# copper.net
KiCad netlist of a schematic drawn in EAGLE
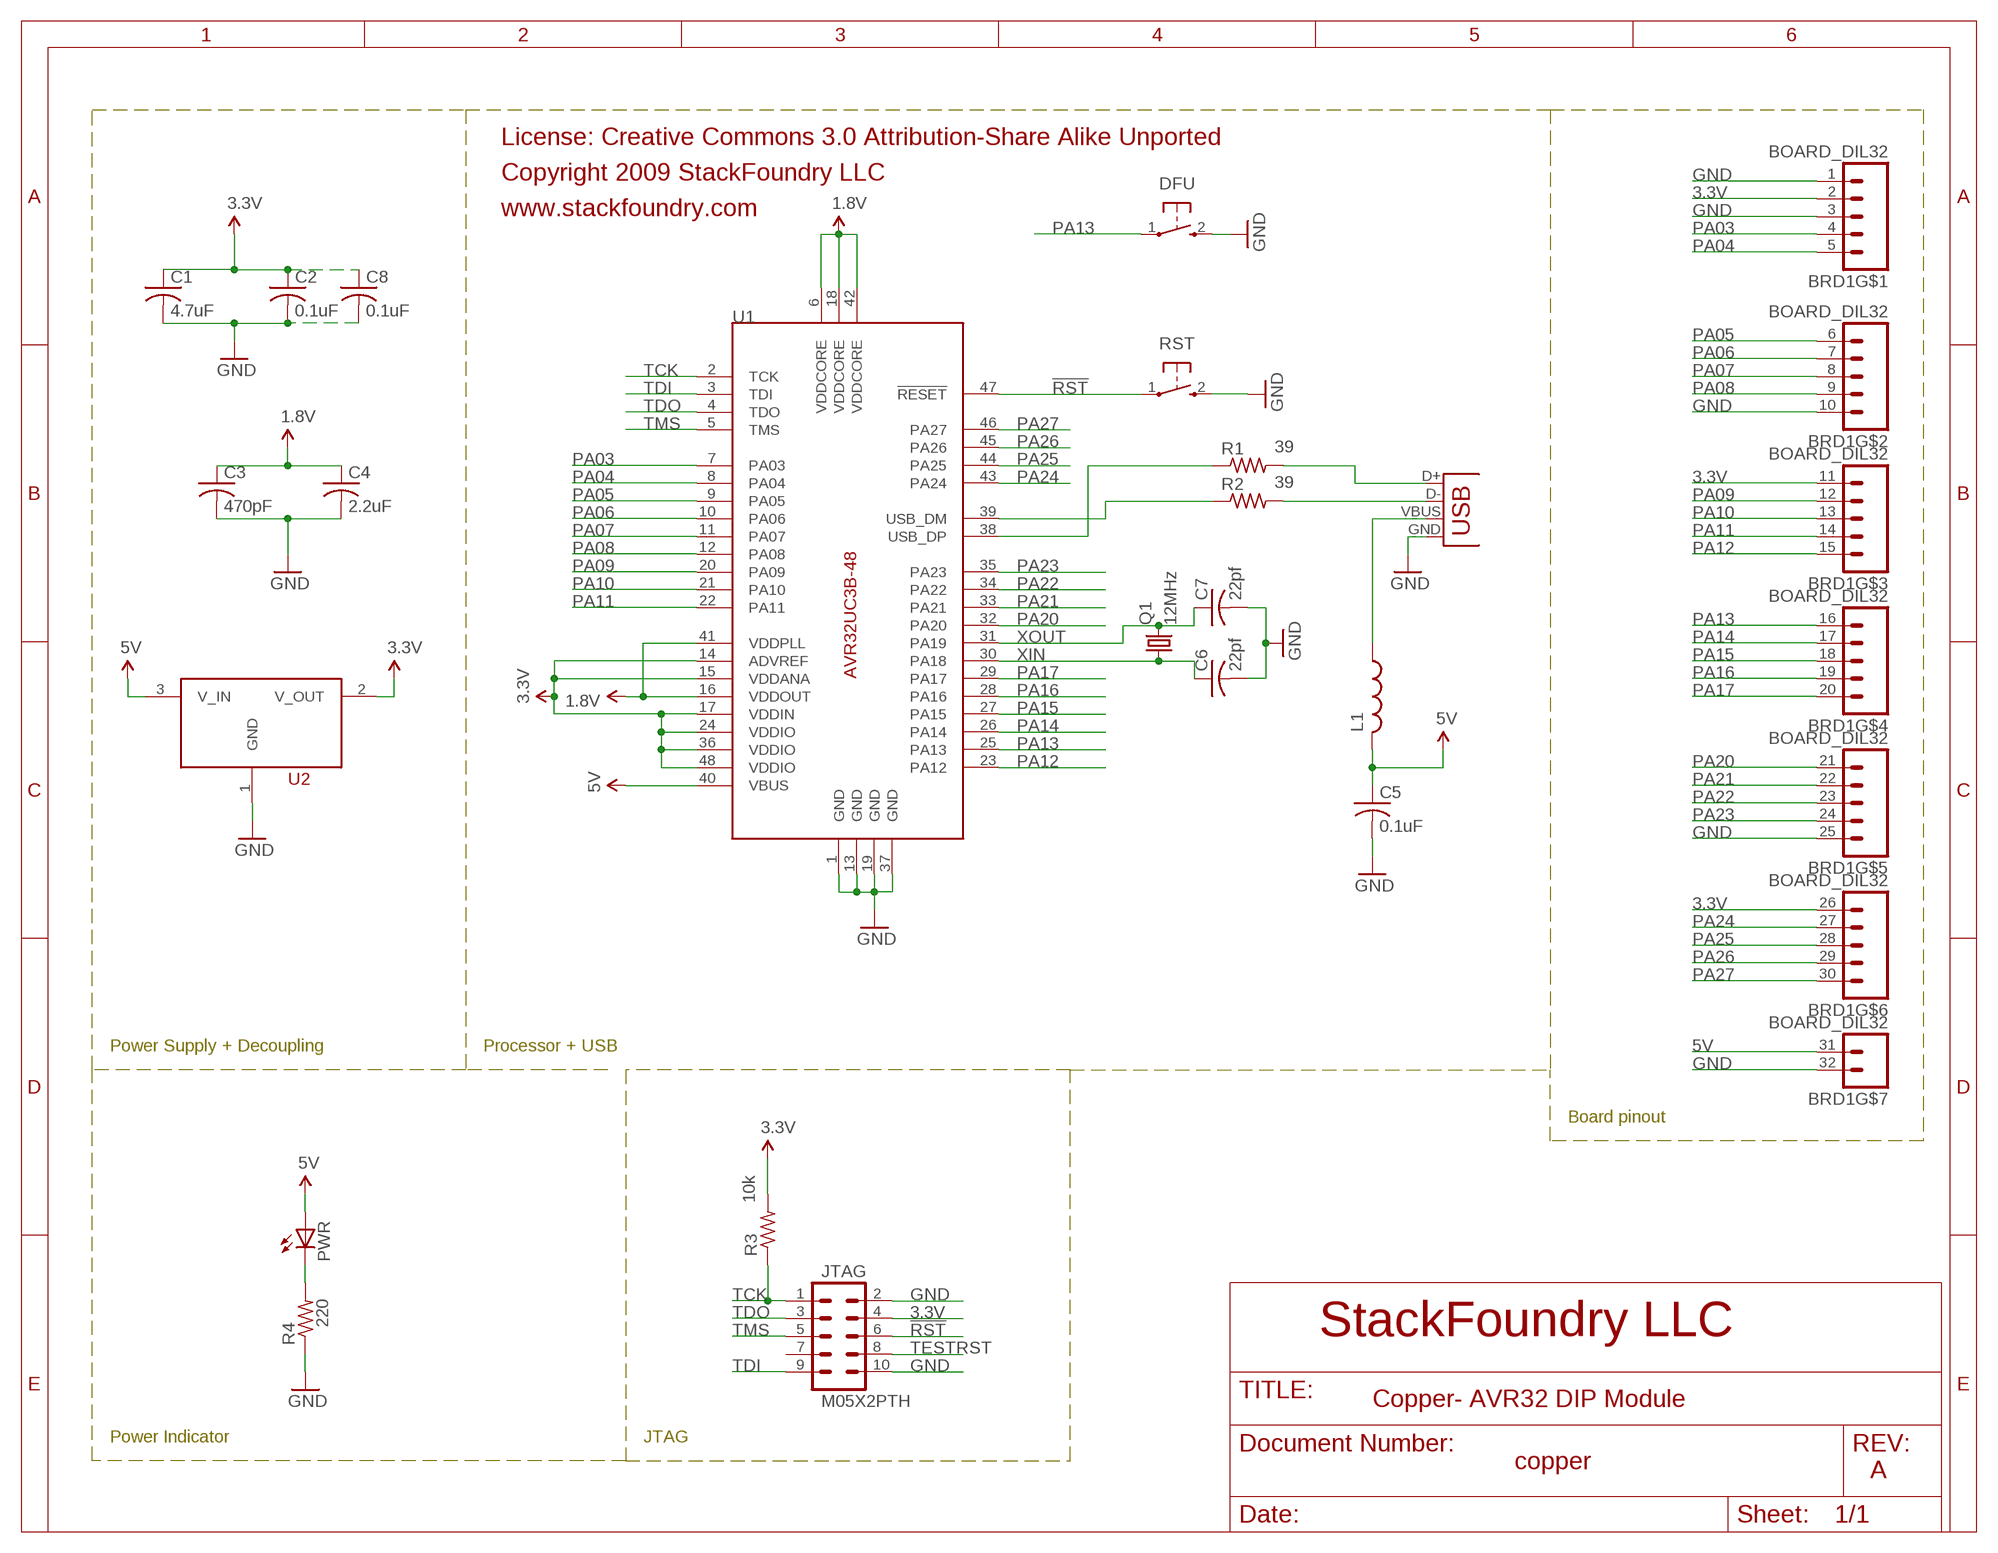
[diagram p0: schematic, sheet 1]

(export (version "E")
  (design (tool "Eeschema 10.0.6"))
  (components
    (comp (ref "BRD1")
      (value "BOARD_DIL32")
      (footprint "eagle-import:DIL32-NOSILK")
      (libsource (lib "eagle-import") (part "BOARD_DIL32"))
    )
    (comp (ref "C1")
      (value "4.7uF")
      (footprint "eagle-import:C0603")
      (libsource (lib "eagle-import") (part "C-USC0603"))
    )
    (comp (ref "C2")
      (value "0.1uF")
      (footprint "eagle-import:C0603")
      (libsource (lib "eagle-import") (part "C-USC0603"))
    )
    (comp (ref "C3")
      (value "470pF")
      (footprint "eagle-import:C0603")
      (libsource (lib "eagle-import") (part "C-USC0603"))
    )
    (comp (ref "C4")
      (value "2.2uF")
      (footprint "eagle-import:C0603")
      (libsource (lib "eagle-import") (part "C-USC0603"))
    )
    (comp (ref "C5")
      (value "0.1uF")
      (footprint "eagle-import:C0603")
      (libsource (lib "eagle-import") (part "C-USC0603"))
    )
    (comp (ref "C6")
      (value "22pf")
      (footprint "eagle-import:C0603")
      (libsource (lib "eagle-import") (part "C-USC0603"))
    )
    (comp (ref "C7")
      (value "22pf")
      (footprint "eagle-import:C0603")
      (libsource (lib "eagle-import") (part "C-USC0603"))
    )
    (comp (ref "C8")
      (value "0.1uF")
      (footprint "eagle-import:C0603")
      (libsource (lib "eagle-import") (part "C-USC0603"))
    )
    (comp (ref "DFU")
      (value "TAC_SWITCH_2PB3U")
      (footprint "eagle-import:OMROM_B3U")
      (libsource (lib "eagle-import") (part "TAC_SWITCH_2PB3U"))
    )
    (comp (ref "JTAG")
      (value "M05X2PTH")
      (footprint "eagle-import:AVR_ICSP")
      (libsource (lib "eagle-import") (part "M05X2PTH"))
    )
    (comp (ref "L1")
      (value "L-USL0805")
      (footprint "eagle-import:L0805")
      (libsource (lib "eagle-import") (part "L-USL0805"))
    )
    (comp (ref "PWR")
      (value "LED1206")
      (footprint "eagle-import:LED-1206")
      (libsource (lib "eagle-import") (part "LED1206"))
    )
    (comp (ref "Q1")
      (value "12MHz")
      (footprint "eagle-import:CRYSTAL-SMD-5X3.2")
      (libsource (lib "eagle-import") (part "CRYSTAL25X3.2"))
    )
    (comp (ref "R1")
      (value "39")
      (footprint "eagle-import:R0603")
      (libsource (lib "eagle-import") (part "R-US_R0603"))
    )
    (comp (ref "R2")
      (value "39")
      (footprint "eagle-import:R0603")
      (libsource (lib "eagle-import") (part "R-US_R0603"))
    )
    (comp (ref "R3")
      (value "10k")
      (footprint "eagle-import:R0603")
      (libsource (lib "eagle-import") (part "R-US_R0603"))
    )
    (comp (ref "R4")
      (value "220")
      (footprint "eagle-import:R0603")
      (libsource (lib "eagle-import") (part "R-US_R0603"))
    )
    (comp (ref "RST")
      (value "TAC_SWITCH_2PB3U")
      (footprint "eagle-import:OMROM_B3U")
      (libsource (lib "eagle-import") (part "TAC_SWITCH_2PB3U"))
    )
    (comp (ref "U1")
      (value "AVR32UC3B-48TQFP")
      (footprint "eagle-import:TQFP48")
      (libsource (lib "eagle-import") (part "AVR32UC3B-48TQFP"))
    )
    (comp (ref "U2")
      (value "MCP1700")
      (footprint "eagle-import:SOT23")
      (libsource (lib "eagle-import") (part "MCP1700"))
    )
    (comp (ref "X2")
      (value "USBSMD")
      (footprint "eagle-import:USB-MINIB")
      (libsource (lib "eagle-import") (part "USBSMD"))
    )
  )
  (nets
    (net (code "1") (name "/PA03") (class "Default")
      (node (ref "BRD1") (pin "4") (pinfunction "4_4") (pintype "passive"))
      (node (ref "U1") (pin "7") (pinfunction "PA03_7") (pintype "bidirectional"))
    )
    (net (code "2") (name "/PA04") (class "Default")
      (node (ref "BRD1") (pin "5") (pinfunction "5_5") (pintype "passive"))
      (node (ref "U1") (pin "8") (pinfunction "PA04_8") (pintype "bidirectional"))
    )
    (net (code "3") (name "/PA05") (class "Default")
      (node (ref "BRD1") (pin "6") (pinfunction "1_6") (pintype "passive"))
      (node (ref "U1") (pin "9") (pinfunction "PA05_9") (pintype "bidirectional"))
    )
    (net (code "4") (name "/PA06") (class "Default")
      (node (ref "BRD1") (pin "7") (pinfunction "2_7") (pintype "passive"))
      (node (ref "U1") (pin "10") (pinfunction "PA06_10") (pintype "bidirectional"))
    )
    (net (code "5") (name "/PA07") (class "Default")
      (node (ref "BRD1") (pin "8") (pinfunction "3_8") (pintype "passive"))
      (node (ref "U1") (pin "11") (pinfunction "PA07_11") (pintype "bidirectional"))
    )
    (net (code "6") (name "/PA08") (class "Default")
      (node (ref "BRD1") (pin "9") (pinfunction "4_9") (pintype "passive"))
      (node (ref "U1") (pin "12") (pinfunction "PA08_12") (pintype "bidirectional"))
    )
    (net (code "7") (name "/PA09") (class "Default")
      (node (ref "BRD1") (pin "12") (pinfunction "2_12") (pintype "passive"))
      (node (ref "U1") (pin "20") (pinfunction "PA09_20") (pintype "bidirectional"))
    )
    (net (code "8") (name "/PA10") (class "Default")
      (node (ref "BRD1") (pin "13") (pinfunction "3_13") (pintype "passive"))
      (node (ref "U1") (pin "21") (pinfunction "PA10_21") (pintype "bidirectional"))
    )
    (net (code "9") (name "/PA11") (class "Default")
      (node (ref "BRD1") (pin "14") (pinfunction "4_14") (pintype "passive"))
      (node (ref "U1") (pin "22") (pinfunction "PA11_22") (pintype "bidirectional"))
    )
    (net (code "10") (name "/PA12") (class "Default")
      (node (ref "BRD1") (pin "15") (pinfunction "5_15") (pintype "passive"))
      (node (ref "U1") (pin "23") (pinfunction "PA12_23") (pintype "bidirectional"))
    )
    (net (code "11") (name "/PA13") (class "Default")
      (node (ref "BRD1") (pin "16") (pinfunction "1_16") (pintype "passive"))
      (node (ref "DFU") (pin "1") (pinfunction "1_1") (pintype "passive"))
      (node (ref "U1") (pin "25") (pinfunction "PA13_25") (pintype "bidirectional"))
    )
    (net (code "12") (name "/PA14") (class "Default")
      (node (ref "BRD1") (pin "17") (pinfunction "2_17") (pintype "passive"))
      (node (ref "U1") (pin "26") (pinfunction "PA14_26") (pintype "bidirectional"))
    )
    (net (code "13") (name "/PA15") (class "Default")
      (node (ref "BRD1") (pin "18") (pinfunction "3_18") (pintype "passive"))
      (node (ref "U1") (pin "27") (pinfunction "PA15_27") (pintype "bidirectional"))
    )
    (net (code "14") (name "/PA16") (class "Default")
      (node (ref "BRD1") (pin "19") (pinfunction "4_19") (pintype "passive"))
      (node (ref "U1") (pin "28") (pinfunction "PA16_28") (pintype "bidirectional"))
    )
    (net (code "15") (name "/PA17") (class "Default")
      (node (ref "BRD1") (pin "20") (pinfunction "5_20") (pintype "passive"))
      (node (ref "U1") (pin "29") (pinfunction "PA17_29") (pintype "bidirectional"))
    )
    (net (code "16") (name "/PA20") (class "Default")
      (node (ref "BRD1") (pin "21") (pinfunction "1_21") (pintype "passive"))
      (node (ref "U1") (pin "32") (pinfunction "PA20_32") (pintype "bidirectional"))
    )
    (net (code "17") (name "/PA21") (class "Default")
      (node (ref "BRD1") (pin "22") (pinfunction "2_22") (pintype "passive"))
      (node (ref "U1") (pin "33") (pinfunction "PA21_33") (pintype "bidirectional"))
    )
    (net (code "18") (name "/PA22") (class "Default")
      (node (ref "BRD1") (pin "23") (pinfunction "3_23") (pintype "passive"))
      (node (ref "U1") (pin "34") (pinfunction "PA22_34") (pintype "bidirectional"))
    )
    (net (code "19") (name "/PA23") (class "Default")
      (node (ref "BRD1") (pin "24") (pinfunction "4_24") (pintype "passive"))
      (node (ref "U1") (pin "35") (pinfunction "PA23_35") (pintype "bidirectional"))
    )
    (net (code "20") (name "/PA24") (class "Default")
      (node (ref "BRD1") (pin "27") (pinfunction "2_27") (pintype "passive"))
      (node (ref "U1") (pin "43") (pinfunction "PA24_43") (pintype "bidirectional"))
    )
    (net (code "21") (name "/PA25") (class "Default")
      (node (ref "BRD1") (pin "28") (pinfunction "3_28") (pintype "passive"))
      (node (ref "U1") (pin "44") (pinfunction "PA25_44") (pintype "bidirectional"))
    )
    (net (code "22") (name "/PA26") (class "Default")
      (node (ref "BRD1") (pin "29") (pinfunction "4_29") (pintype "passive"))
      (node (ref "U1") (pin "45") (pinfunction "PA26_45") (pintype "bidirectional"))
    )
    (net (code "23") (name "/PA27") (class "Default")
      (node (ref "BRD1") (pin "30") (pinfunction "5_30") (pintype "passive"))
      (node (ref "U1") (pin "46") (pinfunction "PA27_46") (pintype "bidirectional"))
    )
    (net (code "24") (name "/TCK") (class "Default")
      (node (ref "JTAG") (pin "1") (pinfunction "1_1") (pintype "passive"))
      (node (ref "R3") (pin "1") (pinfunction "1_1") (pintype "passive"))
      (node (ref "U1") (pin "2") (pinfunction "TCK_2") (pintype "bidirectional"))
    )
    (net (code "25") (name "/TDI") (class "Default")
      (node (ref "JTAG") (pin "9") (pinfunction "9_9") (pintype "passive"))
      (node (ref "U1") (pin "3") (pinfunction "TDI_3") (pintype "bidirectional"))
    )
    (net (code "26") (name "/TDO") (class "Default")
      (node (ref "JTAG") (pin "3") (pinfunction "3_3") (pintype "passive"))
      (node (ref "U1") (pin "4") (pinfunction "TDO_4") (pintype "bidirectional"))
    )
    (net (code "27") (name "/TESTRST") (class "Default")
      (node (ref "JTAG") (pin "8") (pinfunction "8_8") (pintype "passive"))
    )
    (net (code "28") (name "/TMS") (class "Default")
      (node (ref "JTAG") (pin "5") (pinfunction "5_5") (pintype "passive"))
      (node (ref "U1") (pin "5") (pinfunction "TMS_5") (pintype "bidirectional"))
    )
    (net (code "29") (name "/XIN") (class "Default")
      (node (ref "C6") (pin "1") (pinfunction "1_1") (pintype "passive"))
      (node (ref "Q1") (pin "1") (pinfunction "1_1") (pintype "passive"))
      (node (ref "U1") (pin "30") (pinfunction "PA18_30") (pintype "bidirectional"))
    )
    (net (code "30") (name "/XOUT") (class "Default")
      (node (ref "C7") (pin "1") (pinfunction "1_1") (pintype "passive"))
      (node (ref "Q1") (pin "3") (pinfunction "2_3") (pintype "passive"))
      (node (ref "U1") (pin "31") (pinfunction "PA19_31") (pintype "bidirectional"))
    )
    (net (code "31") (name "/~{RST}") (class "Default")
      (node (ref "JTAG") (pin "6") (pinfunction "6_6") (pintype "passive"))
      (node (ref "RST") (pin "1") (pinfunction "1_1") (pintype "passive"))
      (node (ref "U1") (pin "47") (pinfunction "~{RESET}_47") (pintype "bidirectional"))
    )
    (net (code "32") (name "1.8V") (class "Default")
      (node (ref "C3") (pin "1") (pinfunction "1_1") (pintype "passive"))
      (node (ref "C4") (pin "1") (pinfunction "1_1") (pintype "passive"))
      (node (ref "U1") (pin "16") (pinfunction "VDDOUT_16") (pintype "bidirectional"))
      (node (ref "U1") (pin "18") (pinfunction "VDDCORE_18") (pintype "bidirectional"))
      (node (ref "U1") (pin "41") (pinfunction "VDDPLL_41") (pintype "bidirectional"))
      (node (ref "U1") (pin "42") (pinfunction "VDDCORE_42") (pintype "bidirectional"))
      (node (ref "U1") (pin "6") (pinfunction "VDDCORE_6") (pintype "bidirectional"))
    )
    (net (code "33") (name "3.3V") (class "Default")
      (node (ref "BRD1") (pin "11") (pinfunction "1_11") (pintype "passive"))
      (node (ref "BRD1") (pin "2") (pinfunction "2_2") (pintype "passive"))
      (node (ref "BRD1") (pin "26") (pinfunction "1_26") (pintype "passive"))
      (node (ref "C1") (pin "1") (pinfunction "1_1") (pintype "passive"))
      (node (ref "C2") (pin "1") (pinfunction "1_1") (pintype "passive"))
      (node (ref "C8") (pin "1") (pinfunction "1_1") (pintype "passive"))
      (node (ref "JTAG") (pin "4") (pinfunction "4_4") (pintype "passive"))
      (node (ref "R3") (pin "2") (pinfunction "2_2") (pintype "passive"))
      (node (ref "U1") (pin "14") (pinfunction "ADVREF_14") (pintype "bidirectional"))
      (node (ref "U1") (pin "15") (pinfunction "VDDANA_15") (pintype "bidirectional"))
      (node (ref "U1") (pin "17") (pinfunction "VDDIN_17") (pintype "bidirectional"))
      (node (ref "U1") (pin "24") (pinfunction "VDDIO_24") (pintype "bidirectional"))
      (node (ref "U1") (pin "36") (pinfunction "VDDIO_36") (pintype "bidirectional"))
      (node (ref "U1") (pin "48") (pinfunction "VDDIO_48") (pintype "bidirectional"))
      (node (ref "U2") (pin "2") (pinfunction "V_OUT_2") (pintype "bidirectional"))
    )
    (net (code "34") (name "5V") (class "Default")
      (node (ref "BRD1") (pin "31") (pinfunction "1_31") (pintype "passive"))
      (node (ref "C5") (pin "1") (pinfunction "1_1") (pintype "passive"))
      (node (ref "L1") (pin "2") (pinfunction "2_2") (pintype "passive"))
      (node (ref "PWR") (pin "A") (pinfunction "A_A") (pintype "passive"))
      (node (ref "U1") (pin "40") (pinfunction "VBUS_40") (pintype "bidirectional"))
      (node (ref "U2") (pin "3") (pinfunction "V_IN_3") (pintype "bidirectional"))
    )
    (net (code "35") (name "GND") (class "Default")
      (node (ref "BRD1") (pin "1") (pinfunction "1_1") (pintype "passive"))
      (node (ref "BRD1") (pin "10") (pinfunction "5_10") (pintype "passive"))
      (node (ref "BRD1") (pin "25") (pinfunction "5_25") (pintype "passive"))
      (node (ref "BRD1") (pin "3") (pinfunction "3_3") (pintype "passive"))
      (node (ref "BRD1") (pin "32") (pinfunction "2_32") (pintype "passive"))
      (node (ref "C1") (pin "2") (pinfunction "2_2") (pintype "passive"))
      (node (ref "C2") (pin "2") (pinfunction "2_2") (pintype "passive"))
      (node (ref "C3") (pin "2") (pinfunction "2_2") (pintype "passive"))
      (node (ref "C4") (pin "2") (pinfunction "2_2") (pintype "passive"))
      (node (ref "C5") (pin "2") (pinfunction "2_2") (pintype "passive"))
      (node (ref "C6") (pin "2") (pinfunction "2_2") (pintype "passive"))
      (node (ref "C7") (pin "2") (pinfunction "2_2") (pintype "passive"))
      (node (ref "C8") (pin "2") (pinfunction "2_2") (pintype "passive"))
      (node (ref "DFU") (pin "2") (pinfunction "3_2") (pintype "passive"))
      (node (ref "JTAG") (pin "10") (pinfunction "10_10") (pintype "passive"))
      (node (ref "JTAG") (pin "2") (pinfunction "2_2") (pintype "passive"))
      (node (ref "R4") (pin "1") (pinfunction "1_1") (pintype "passive"))
      (node (ref "RST") (pin "2") (pinfunction "3_2") (pintype "passive"))
      (node (ref "U1") (pin "1") (pinfunction "GND_1") (pintype "bidirectional"))
      (node (ref "U1") (pin "13") (pinfunction "GND_13") (pintype "bidirectional"))
      (node (ref "U1") (pin "19") (pinfunction "GND_19") (pintype "bidirectional"))
      (node (ref "U1") (pin "37") (pinfunction "GND_37") (pintype "bidirectional"))
      (node (ref "U2") (pin "1") (pinfunction "GND_1") (pintype "bidirectional"))
      (node (ref "X2") (pin "GND") (pinfunction "GND_GND") (pintype "bidirectional"))
    )
    (net (code "36") (name "Net-(L1-Pad1)") (class "Default")
      (node (ref "L1") (pin "1") (pinfunction "1_1") (pintype "passive"))
      (node (ref "X2") (pin "VBUS") (pinfunction "VBUS_VBUS") (pintype "bidirectional"))
    )
    (net (code "37") (name "Net-(PWR-PadC)") (class "Default")
      (node (ref "PWR") (pin "C") (pinfunction "C_C") (pintype "passive"))
      (node (ref "R4") (pin "2") (pinfunction "2_2") (pintype "passive"))
    )
    (net (code "38") (name "Net-(R1-Pad2)") (class "Default")
      (node (ref "R1") (pin "2") (pinfunction "2_2") (pintype "passive"))
      (node (ref "X2") (pin "D+") (pinfunction "D+_D+") (pintype "bidirectional"))
    )
    (net (code "39") (name "Net-(R2-Pad2)") (class "Default")
      (node (ref "R2") (pin "2") (pinfunction "2_2") (pintype "passive"))
      (node (ref "X2") (pin "D-") (pinfunction "D-_D-") (pintype "bidirectional"))
    )
    (net (code "40") (name "Net-(U1-USB_DM)") (class "Default")
      (node (ref "R2") (pin "1") (pinfunction "1_1") (pintype "passive"))
      (node (ref "U1") (pin "39") (pinfunction "USB_DM_39") (pintype "bidirectional"))
    )
    (net (code "41") (name "Net-(U1-USB_DP)") (class "Default")
      (node (ref "R1") (pin "1") (pinfunction "1_1") (pintype "passive"))
      (node (ref "U1") (pin "38") (pinfunction "USB_DP_38") (pintype "bidirectional"))
    )
    (net (code "42") (name "unconnected-(JTAG-Pad7)") (class "Default")
      (node (ref "JTAG") (pin "7") (pinfunction "7_7") (pintype "passive"))
    )
  )
)
